# 555_projects_grove_i2c_ldr_revA.net
KiCad netlist of a schematic drawn in EAGLE
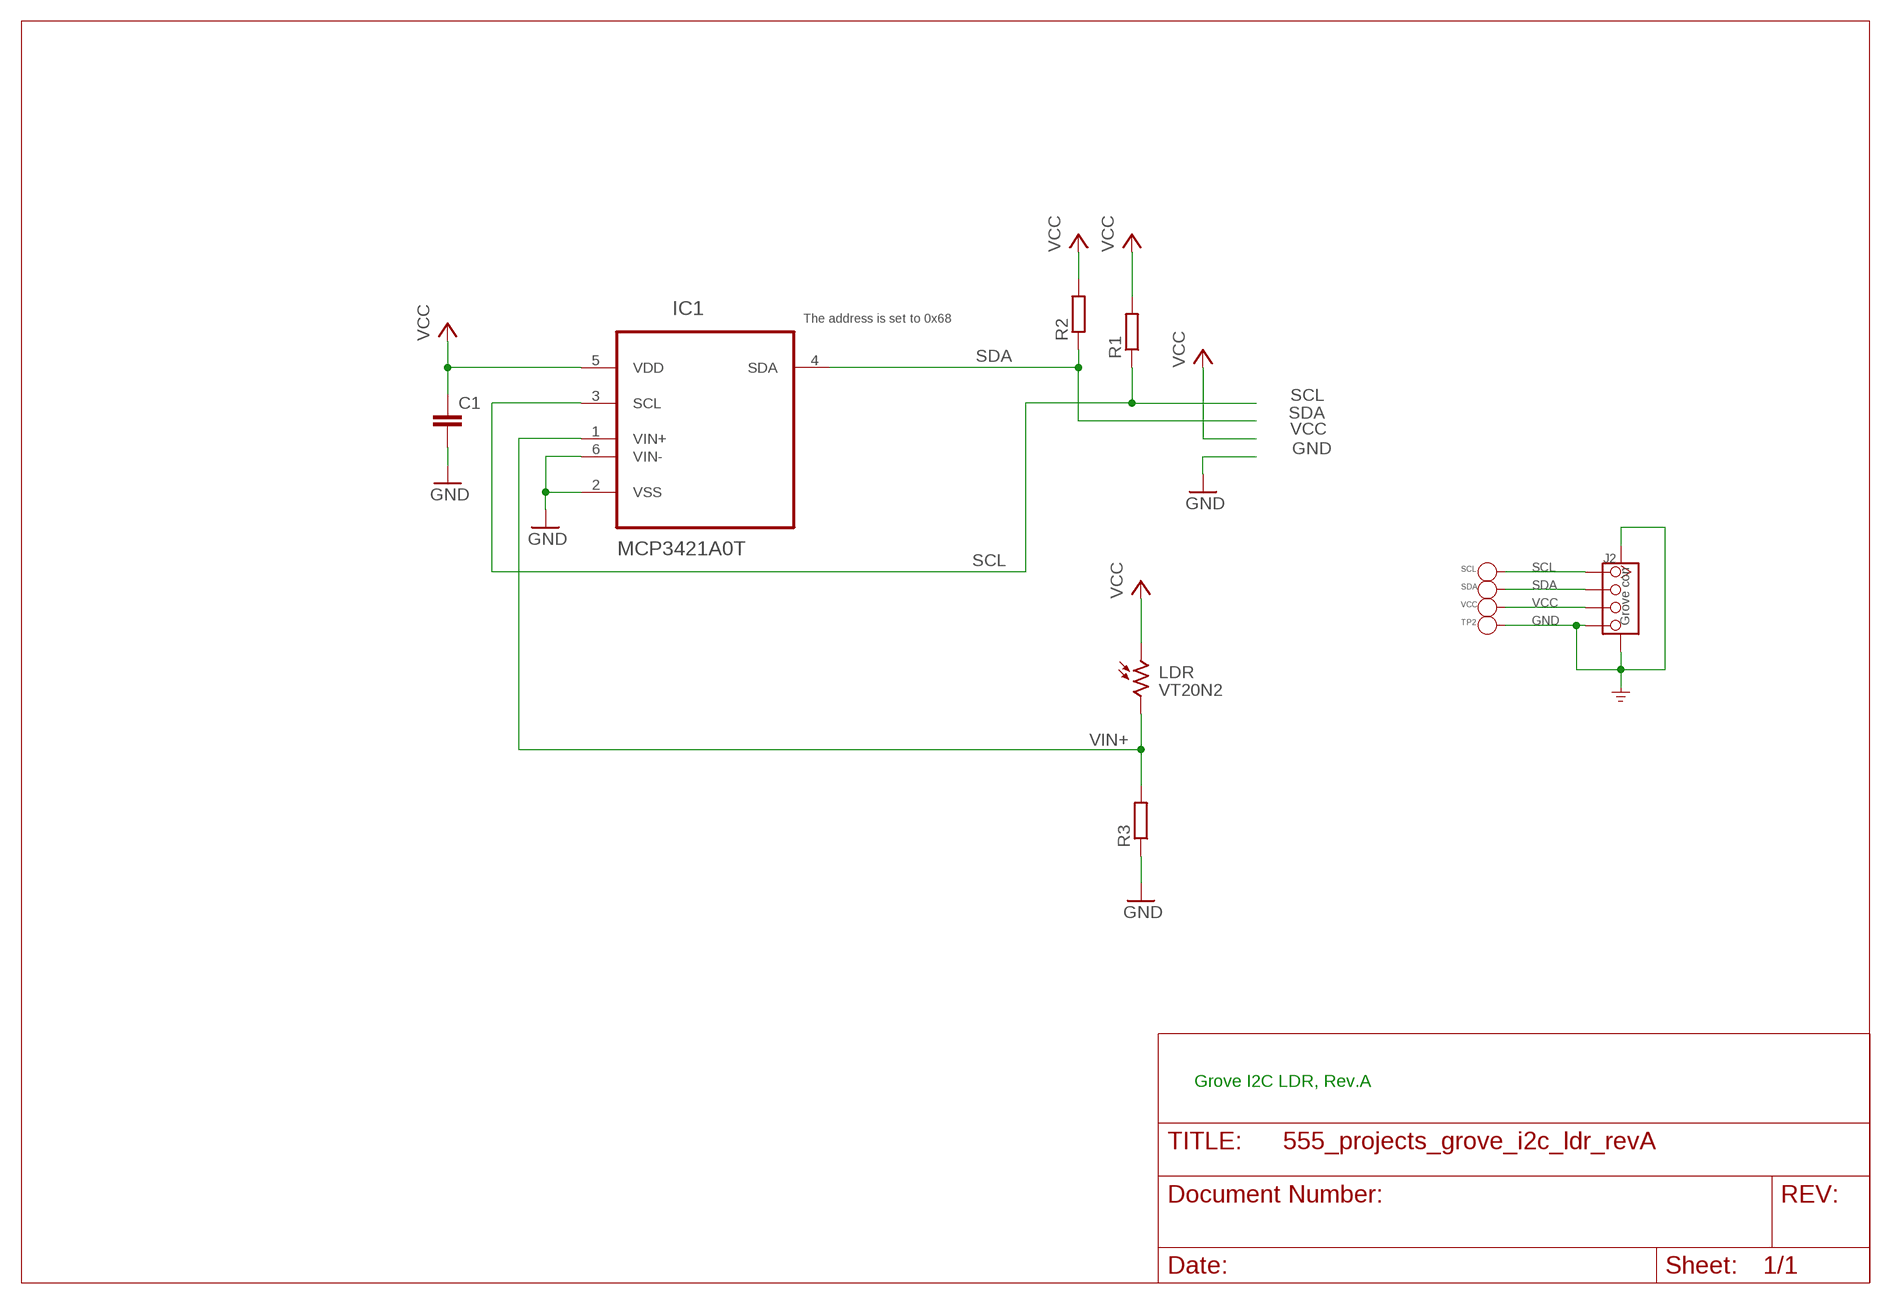
[diagram p0: schematic, sheet 1]

(export (version "E")
  (design (tool "Eeschema 10.0.6"))
  (components
    (comp (ref "C1")
      (value "C-EUC0805K")
      (footprint "eagle-import:C0805K")
      (libsource (lib "eagle-import") (part "C-EUC0805K"))
    )
    (comp (ref "IC1")
      (value "MCP3421A0T")
      (footprint "eagle-import:SOT95P270X145-6N")
      (fields (field (name "MPN") "MCP3421A0T-E/CH"))
      (libsource (lib "eagle-import") (part "MCP3421A0T-E/CH"))
    )
    (comp (ref "J2")
      (value "Grove con")
      (footprint "eagle-import:4P-SMD-2.0")
      (libsource (lib "eagle-import") (part "TWIG-4P-2.0-SMD-FEMALE-REINFORCE'DD'"))
    )
    (comp (ref "LDR")
      (value "VT20N2")
      (footprint "eagle-import:TO46-VT200")
      (libsource (lib "eagle-import") (part "VT20N2"))
    )
    (comp (ref "R1")
      (value "R-EU_R0805")
      (footprint "eagle-import:R0805")
      (libsource (lib "eagle-import") (part "R-EU_R0805"))
    )
    (comp (ref "R2")
      (value "R-EU_R0805")
      (footprint "eagle-import:R0805")
      (libsource (lib "eagle-import") (part "R-EU_R0805"))
    )
    (comp (ref "R3")
      (value "R-EU_R0805")
      (footprint "eagle-import:R0805")
      (libsource (lib "eagle-import") (part "R-EU_R0805"))
    )
    (comp (ref "SCL")
      (value "TP3")
      (footprint "eagle-import:TP_4545")
      (fields (field (name "PARTNO") "DNP"))
      (libsource (lib "eagle-import") (part "PAD-TEST-POINT'4545'"))
    )
    (comp (ref "SDA")
      (value "TP3")
      (footprint "eagle-import:TP_4545")
      (fields (field (name "PARTNO") "DNP"))
      (libsource (lib "eagle-import") (part "PAD-TEST-POINT'4545'"))
    )
    (comp (ref "TP2")
      (value "PAD-TEST-POINT'4545'")
      (footprint "eagle-import:TP_4545")
      (fields (field (name "PARTNO") "DNP"))
      (libsource (lib "eagle-import") (part "PAD-TEST-POINT'4545'"))
    )
    (comp (ref "VCC")
      (value "TP2")
      (footprint "eagle-import:TP_4545")
      (fields (field (name "PARTNO") "DNP"))
      (libsource (lib "eagle-import") (part "PAD-TEST-POINT'4545'"))
    )
  )
  (nets
    (net (code "1") (name "/SCL") (class "Default")
      (node (ref "IC1") (pin "3") (pinfunction "SCL_3") (pintype "input"))
      (node (ref "J2") (pin "1") (pinfunction "1_1") (pintype "bidirectional"))
      (node (ref "R1") (pin "1") (pinfunction "1_1") (pintype "passive"))
      (node (ref "SCL") (pin "T") (pinfunction "T_T") (pintype "bidirectional"))
    )
    (net (code "2") (name "/SDA") (class "Default")
      (node (ref "IC1") (pin "4") (pinfunction "SDA_4") (pintype "bidirectional"))
      (node (ref "J2") (pin "2") (pinfunction "2_2") (pintype "bidirectional"))
      (node (ref "R2") (pin "1") (pinfunction "1_1") (pintype "passive"))
      (node (ref "SDA") (pin "T") (pinfunction "T_T") (pintype "bidirectional"))
    )
    (net (code "3") (name "/VIN+") (class "Default")
      (node (ref "IC1") (pin "1") (pinfunction "VIN+_1") (pintype "input"))
      (node (ref "LDR") (pin "2") (pinfunction "2_2") (pintype "passive"))
      (node (ref "R3") (pin "2") (pinfunction "2_2") (pintype "passive"))
    )
    (net (code "4") (name "GND") (class "Default")
      (node (ref "C1") (pin "2") (pinfunction "2_2") (pintype "passive"))
      (node (ref "IC1") (pin "2") (pinfunction "VSS_2") (pintype "passive"))
      (node (ref "IC1") (pin "6") (pinfunction "VIN-_6") (pintype "input"))
      (node (ref "J2") (pin "4") (pinfunction "4_4") (pintype "bidirectional"))
      (node (ref "J2") (pin "SS1") (pinfunction "SS1_SS1") (pintype "bidirectional"))
      (node (ref "J2") (pin "SS2") (pinfunction "SS2_SS2") (pintype "bidirectional"))
      (node (ref "R3") (pin "1") (pinfunction "1_1") (pintype "passive"))
      (node (ref "TP2") (pin "T") (pinfunction "T_T") (pintype "bidirectional"))
    )
    (net (code "5") (name "VCC") (class "Default")
      (node (ref "C1") (pin "1") (pinfunction "1_1") (pintype "passive"))
      (node (ref "IC1") (pin "5") (pinfunction "VDD_5") (pintype "power_in"))
      (node (ref "J2") (pin "3") (pinfunction "3_3") (pintype "bidirectional"))
      (node (ref "LDR") (pin "1") (pinfunction "1_1") (pintype "passive"))
      (node (ref "R1") (pin "2") (pinfunction "2_2") (pintype "passive"))
      (node (ref "R2") (pin "2") (pinfunction "2_2") (pintype "passive"))
      (node (ref "VCC") (pin "T") (pinfunction "T_T") (pintype "bidirectional"))
    )
  )
)
